# 6_Analog.net
KiCad netlist of a schematic drawn in Altium Designer
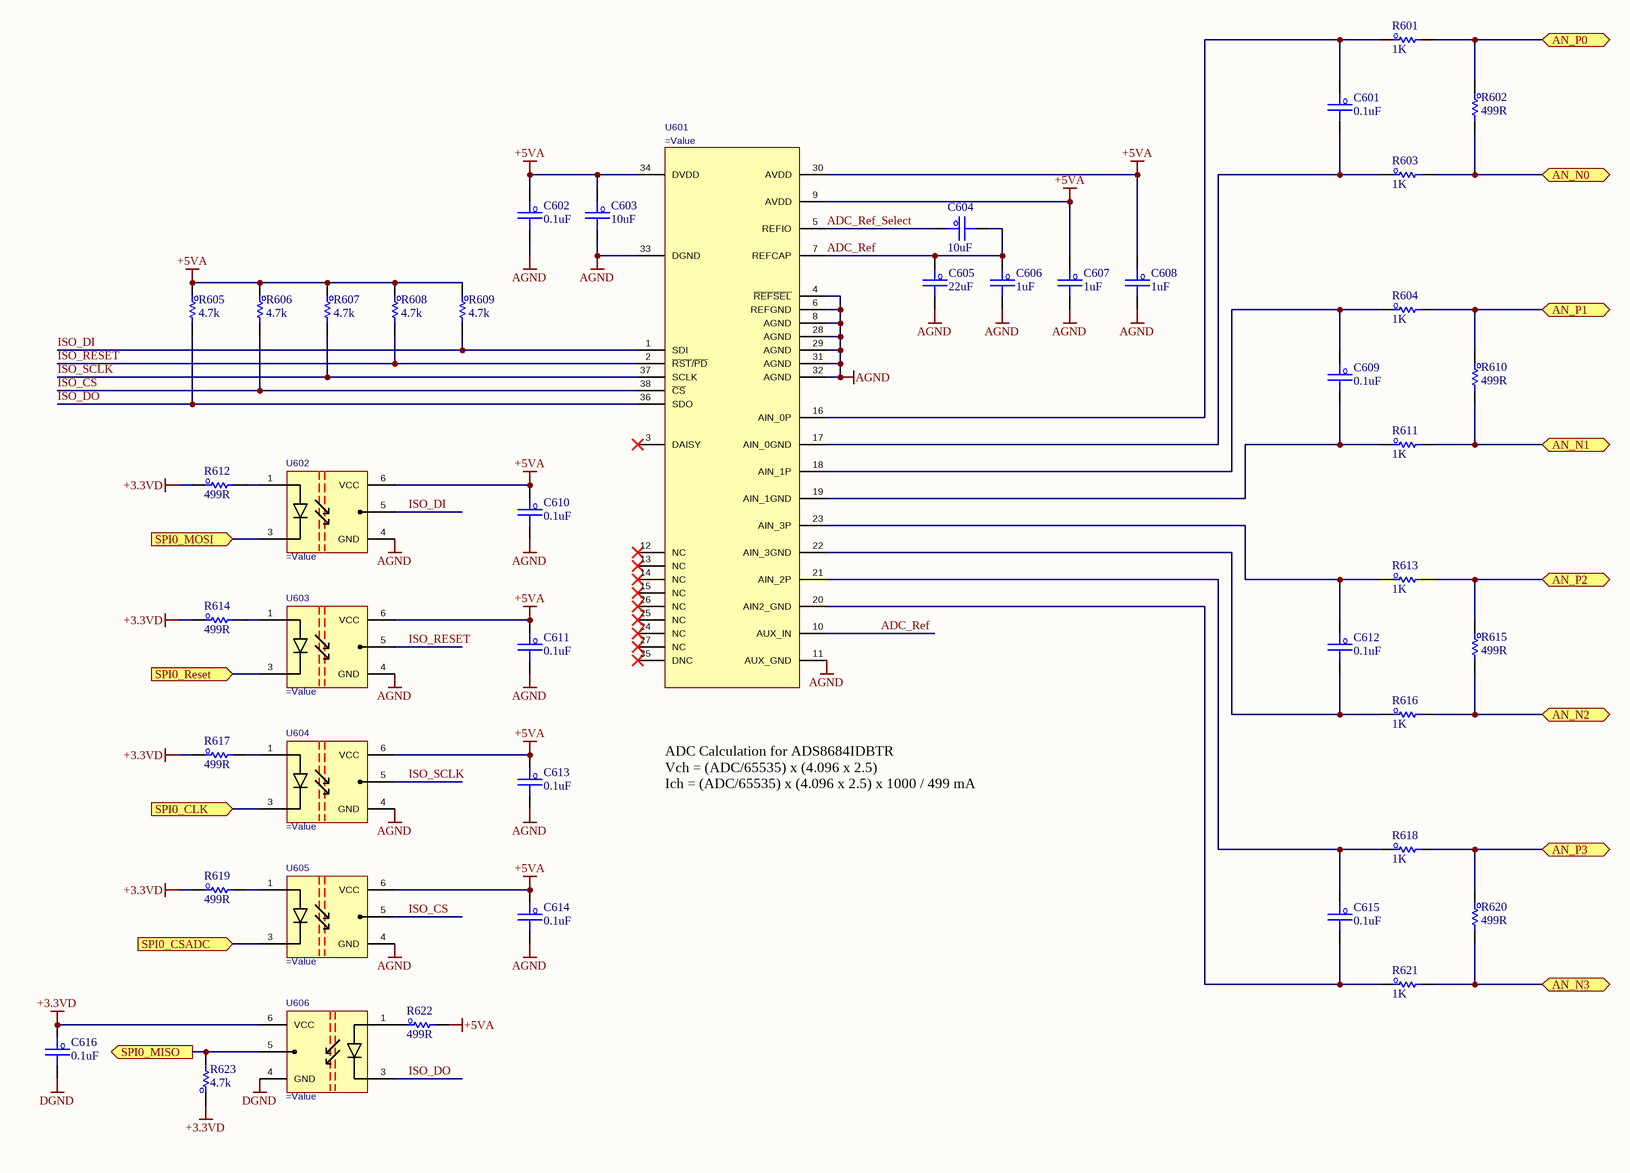
[diagram p0: 6_Analog.SchDoc]

(export (version "E")
  (design (tool "Eeschema 10.0.6"))
  (components
    (comp (ref "C601")
      (value "0.1uF")
      (footprint "C_0603")
      (description "CAP CER 0.1UF 50V X7R 0603")
      (fields (field (name "MANUFACTURER") "KEMET") (field (name "PARTNUMBER") "C0603C104K5RACTU"))
      (libsource (lib "UUSymbol") (part "C_Capacitor"))
    )
    (comp (ref "C602")
      (value "0.1uF")
      (footprint "C_0603")
      (description "CAP CER 0.1UF 50V X7R 0603")
      (fields (field (name "MANUFACTURER") "KEMET") (field (name "PARTNUMBER") "C0603C104K5RACTU"))
      (libsource (lib "UUSymbol") (part "C_Capacitor"))
    )
    (comp (ref "C603")
      (value "10uF")
      (footprint "C_0603")
      (description "CAP CER 10UF 10V X6S 0603")
      (fields
        (field (name "MANUFACTURER") "Murata Electronics")
        (field (name "PARTNUMBER") "GRT188C81A106ME13D")
      )
      (libsource (lib "UUSymbol") (part "C_Capacitor"))
    )
    (comp (ref "C604")
      (value "10uF")
      (footprint "C_0603")
      (description "CAP CER 10UF 10V X6S 0603")
      (fields
        (field (name "MANUFACTURER") "Murata Electronics")
        (field (name "PARTNUMBER") "GRT188C81A106ME13D")
      )
      (libsource (lib "UUSymbol") (part "C_Capacitor"))
    )
    (comp (ref "C605")
      (value "22uF")
      (footprint "C_0603")
      (description "CAP CER 22UF 10V X5R 0603")
      (fields
        (field (name "MANUFACTURER") "Murata Electronics")
        (field (name "PARTNUMBER") "GRM187R61A226ME15D")
      )
      (libsource (lib "UUSymbol") (part "C_Capacitor"))
    )
    (comp (ref "C606")
      (value "1uF")
      (footprint "C_0603")
      (description "CAP CER 1UF 50V X5R 0603")
      (fields
        (field (name "MANUFACTURER") "Murata Electronics")
        (field (name "PARTNUMBER") "GRT188R61H105KE13D")
      )
      (libsource (lib "UUSymbol") (part "C_Capacitor"))
    )
    (comp (ref "C607")
      (value "1uF")
      (footprint "C_0603")
      (description "CAP CER 1UF 50V X5R 0603")
      (fields
        (field (name "MANUFACTURER") "Murata Electronics")
        (field (name "PARTNUMBER") "GRT188R61H105KE13D")
      )
      (libsource (lib "UUSymbol") (part "C_Capacitor"))
    )
    (comp (ref "C608")
      (value "1uF")
      (footprint "C_0603")
      (description "CAP CER 1UF 50V X5R 0603")
      (fields
        (field (name "MANUFACTURER") "Murata Electronics")
        (field (name "PARTNUMBER") "GRT188R61H105KE13D")
      )
      (libsource (lib "UUSymbol") (part "C_Capacitor"))
    )
    (comp (ref "C609")
      (value "0.1uF")
      (footprint "C_0603")
      (description "CAP CER 0.1UF 50V X7R 0603")
      (fields (field (name "MANUFACTURER") "KEMET") (field (name "PARTNUMBER") "C0603C104K5RACTU"))
      (libsource (lib "UUSymbol") (part "C_Capacitor"))
    )
    (comp (ref "C610")
      (value "0.1uF")
      (footprint "C_0603")
      (description "CAP CER 0.1UF 50V X7R 0603")
      (fields (field (name "MANUFACTURER") "KEMET") (field (name "PARTNUMBER") "C0603C104K5RACTU"))
      (libsource (lib "UUSymbol") (part "C_Capacitor"))
    )
    (comp (ref "C611")
      (value "0.1uF")
      (footprint "C_0603")
      (description "CAP CER 0.1UF 50V X7R 0603")
      (fields (field (name "MANUFACTURER") "KEMET") (field (name "PARTNUMBER") "C0603C104K5RACTU"))
      (libsource (lib "UUSymbol") (part "C_Capacitor"))
    )
    (comp (ref "C612")
      (value "0.1uF")
      (footprint "C_0603")
      (description "CAP CER 0.1UF 50V X7R 0603")
      (fields (field (name "MANUFACTURER") "KEMET") (field (name "PARTNUMBER") "C0603C104K5RACTU"))
      (libsource (lib "UUSymbol") (part "C_Capacitor"))
    )
    (comp (ref "C613")
      (value "0.1uF")
      (footprint "C_0603")
      (description "CAP CER 0.1UF 50V X7R 0603")
      (fields (field (name "MANUFACTURER") "KEMET") (field (name "PARTNUMBER") "C0603C104K5RACTU"))
      (libsource (lib "UUSymbol") (part "C_Capacitor"))
    )
    (comp (ref "C614")
      (value "0.1uF")
      (footprint "C_0603")
      (description "CAP CER 0.1UF 50V X7R 0603")
      (fields (field (name "MANUFACTURER") "KEMET") (field (name "PARTNUMBER") "C0603C104K5RACTU"))
      (libsource (lib "UUSymbol") (part "C_Capacitor"))
    )
    (comp (ref "C615")
      (value "0.1uF")
      (footprint "C_0603")
      (description "CAP CER 0.1UF 50V X7R 0603")
      (fields (field (name "MANUFACTURER") "KEMET") (field (name "PARTNUMBER") "C0603C104K5RACTU"))
      (libsource (lib "UUSymbol") (part "C_Capacitor"))
    )
    (comp (ref "C616")
      (value "0.1uF")
      (footprint "C_0603")
      (description "CAP CER 0.1UF 50V X7R 0603")
      (fields (field (name "MANUFACTURER") "KEMET") (field (name "PARTNUMBER") "C0603C104K5RACTU"))
      (libsource (lib "UUSymbol") (part "C_Capacitor"))
    )
    (comp (ref "R601")
      (value "1K")
      (footprint "R_0603")
      (description "RES SMD 1K OHM 5% 1/10W 0603")
      (fields (field (name "MANUFACTURER") "Vishay Dale") (field (name "PARTNUMBER") "CRCW06031K00JNEA"))
      (libsource (lib "UUSymbol") (part "R_Resister"))
    )
    (comp (ref "R602")
      (value "499R")
      (footprint "R_0603")
      (description "RES SMD 499 OHM 1% 1/3W 0603")
      (fields (field (name "MANUFACTURER") "Vishay Dale") (field (name "PARTNUMBER") "CRCW0603499RFKEAHP"))
      (libsource (lib "UUSymbol") (part "R_Resister"))
    )
    (comp (ref "R603")
      (value "1K")
      (footprint "R_0603")
      (description "RES SMD 1K OHM 5% 1/10W 0603")
      (fields (field (name "MANUFACTURER") "Vishay Dale") (field (name "PARTNUMBER") "CRCW06031K00JNEA"))
      (libsource (lib "UUSymbol") (part "R_Resister"))
    )
    (comp (ref "R604")
      (value "1K")
      (footprint "R_0603")
      (description "RES SMD 1K OHM 5% 1/10W 0603")
      (fields (field (name "MANUFACTURER") "Vishay Dale") (field (name "PARTNUMBER") "CRCW06031K00JNEA"))
      (libsource (lib "UUSymbol") (part "R_Resister"))
    )
    (comp (ref "R605")
      (value "4.7k")
      (footprint "R_0603")
      (description "RES 4.7K OHM 5% 1/10W 0603")
      (fields (field (name "MANUFACTURER") "Vishay Dale") (field (name "PARTNUMBER") "CRCW06034K70JNEBC"))
      (libsource (lib "UUSymbol") (part "R_Resister"))
    )
    (comp (ref "R606")
      (value "4.7k")
      (footprint "R_0603")
      (description "RES 4.7K OHM 5% 1/10W 0603")
      (fields (field (name "MANUFACTURER") "Vishay Dale") (field (name "PARTNUMBER") "CRCW06034K70JNEBC"))
      (libsource (lib "UUSymbol") (part "R_Resister"))
    )
    (comp (ref "R607")
      (value "4.7k")
      (footprint "R_0603")
      (description "RES 4.7K OHM 5% 1/10W 0603")
      (fields (field (name "MANUFACTURER") "Vishay Dale") (field (name "PARTNUMBER") "CRCW06034K70JNEBC"))
      (libsource (lib "UUSymbol") (part "R_Resister"))
    )
    (comp (ref "R608")
      (value "4.7k")
      (footprint "R_0603")
      (description "RES 4.7K OHM 5% 1/10W 0603")
      (fields (field (name "MANUFACTURER") "Vishay Dale") (field (name "PARTNUMBER") "CRCW06034K70JNEBC"))
      (libsource (lib "UUSymbol") (part "R_Resister"))
    )
    (comp (ref "R609")
      (value "4.7k")
      (footprint "R_0603")
      (description "RES 4.7K OHM 5% 1/10W 0603")
      (fields (field (name "MANUFACTURER") "Vishay Dale") (field (name "PARTNUMBER") "CRCW06034K70JNEBC"))
      (libsource (lib "UUSymbol") (part "R_Resister"))
    )
    (comp (ref "R610")
      (value "499R")
      (footprint "R_0603")
      (description "RES SMD 499 OHM 1% 1/3W 0603")
      (fields (field (name "MANUFACTURER") "Vishay Dale") (field (name "PARTNUMBER") "CRCW0603499RFKEAHP"))
      (libsource (lib "UUSymbol") (part "R_Resister"))
    )
    (comp (ref "R611")
      (value "1K")
      (footprint "R_0603")
      (description "RES SMD 1K OHM 5% 1/10W 0603")
      (fields (field (name "MANUFACTURER") "Vishay Dale") (field (name "PARTNUMBER") "CRCW06031K00JNEA"))
      (libsource (lib "UUSymbol") (part "R_Resister"))
    )
    (comp (ref "R612")
      (value "499R")
      (footprint "R_0603")
      (description "RES 499 OHM 1% 1/10W 0603")
      (fields (field (name "MANUFACTURER") "Vishay Dale") (field (name "PARTNUMBER") "CRCW0603499RFKEAC"))
      (libsource (lib "UUSymbol") (part "R_Resister"))
    )
    (comp (ref "R613")
      (value "1K")
      (footprint "R_0603")
      (description "RES SMD 1K OHM 5% 1/10W 0603")
      (fields (field (name "MANUFACTURER") "Vishay Dale") (field (name "PARTNUMBER") "CRCW06031K00JNEA"))
      (libsource (lib "UUSymbol") (part "R_Resister"))
    )
    (comp (ref "R614")
      (value "499R")
      (footprint "R_0603")
      (description "RES 499 OHM 1% 1/10W 0603")
      (fields (field (name "MANUFACTURER") "Vishay Dale") (field (name "PARTNUMBER") "CRCW0603499RFKEAC"))
      (libsource (lib "UUSymbol") (part "R_Resister"))
    )
    (comp (ref "R615")
      (value "499R")
      (footprint "R_0603")
      (description "RES SMD 499 OHM 1% 1/3W 0603")
      (fields (field (name "MANUFACTURER") "Vishay Dale") (field (name "PARTNUMBER") "CRCW0603499RFKEAHP"))
      (libsource (lib "UUSymbol") (part "R_Resister"))
    )
    (comp (ref "R616")
      (value "1K")
      (footprint "R_0603")
      (description "RES SMD 1K OHM 5% 1/10W 0603")
      (fields (field (name "MANUFACTURER") "Vishay Dale") (field (name "PARTNUMBER") "CRCW06031K00JNEA"))
      (libsource (lib "UUSymbol") (part "R_Resister"))
    )
    (comp (ref "R617")
      (value "499R")
      (footprint "R_0603")
      (description "RES 499 OHM 1% 1/10W 0603")
      (fields (field (name "MANUFACTURER") "Vishay Dale") (field (name "PARTNUMBER") "CRCW0603499RFKEAC"))
      (libsource (lib "UUSymbol") (part "R_Resister"))
    )
    (comp (ref "R618")
      (value "1K")
      (footprint "R_0603")
      (description "RES SMD 1K OHM 5% 1/10W 0603")
      (fields (field (name "MANUFACTURER") "Vishay Dale") (field (name "PARTNUMBER") "CRCW06031K00JNEA"))
      (libsource (lib "UUSymbol") (part "R_Resister"))
    )
    (comp (ref "R619")
      (value "499R")
      (footprint "R_0603")
      (description "RES 499 OHM 1% 1/10W 0603")
      (fields (field (name "MANUFACTURER") "Vishay Dale") (field (name "PARTNUMBER") "CRCW0603499RFKEAC"))
      (libsource (lib "UUSymbol") (part "R_Resister"))
    )
    (comp (ref "R620")
      (value "499R")
      (footprint "R_0603")
      (description "RES SMD 499 OHM 1% 1/3W 0603")
      (fields (field (name "MANUFACTURER") "Vishay Dale") (field (name "PARTNUMBER") "CRCW0603499RFKEAHP"))
      (libsource (lib "UUSymbol") (part "R_Resister"))
    )
    (comp (ref "R621")
      (value "1K")
      (footprint "R_0603")
      (description "RES SMD 1K OHM 5% 1/10W 0603")
      (fields (field (name "MANUFACTURER") "Vishay Dale") (field (name "PARTNUMBER") "CRCW06031K00JNEA"))
      (libsource (lib "UUSymbol") (part "R_Resister"))
    )
    (comp (ref "R622")
      (value "499R")
      (footprint "R_0603")
      (description "RES 499 OHM 1% 1/10W 0603")
      (fields (field (name "MANUFACTURER") "Vishay Dale") (field (name "PARTNUMBER") "CRCW0603499RFKEAC"))
      (libsource (lib "UUSymbol") (part "R_Resister"))
    )
    (comp (ref "R623")
      (value "4.7k")
      (footprint "R_0603")
      (description "RES 4.7K OHM 5% 1/10W 0603")
      (fields (field (name "MANUFACTURER") "Vishay Dale") (field (name "PARTNUMBER") "CRCW06034K70JNEBC"))
      (libsource (lib "UUSymbol") (part "R_Resister"))
    )
    (comp (ref "U601")
      (value "~")
      (footprint "DBT0038A_N_TEX")
      (description "IC ADC 16BIT SAR 38TSSOP")
      (fields (field (name "MANUFACTURER") "Texas Instruments") (field (name "PARTNUMBER") "ADS8684IDBTR"))
      (libsource (lib "UUSymbol") (part "IC_ADC_ADS8684IDBTR"))
    )
    (comp (ref "U602")
      (value "~")
      (footprint "5PIN SO6_TOS")
      (description "OPTOISO 5KV PUSH PULL SO6L")
      (fields
        (field (name "MANUFACTURER") "Toshiba Semiconductor and Storage")
        (field (name "PARTNUMBER") "TLP2362(TPL,E(T")
      )
      (libsource (lib "") (part "IC_OPTO_TLP109(TPR,E)_1"))
    )
    (comp (ref "U603")
      (value "~")
      (footprint "5PIN SO6_TOS")
      (description "OPTOISO 5KV PUSH PULL SO6L")
      (fields
        (field (name "MANUFACTURER") "Toshiba Semiconductor and Storage")
        (field (name "PARTNUMBER") "TLP2362(TPL,E(T")
      )
      (libsource (lib "") (part "IC_OPTO_TLP109(TPR,E)_1"))
    )
    (comp (ref "U604")
      (value "~")
      (footprint "5PIN SO6_TOS")
      (description "OPTOISO 5KV PUSH PULL SO6L")
      (fields
        (field (name "MANUFACTURER") "Toshiba Semiconductor and Storage")
        (field (name "PARTNUMBER") "TLP2362(TPL,E(T")
      )
      (libsource (lib "") (part "IC_OPTO_TLP109(TPR,E)_1"))
    )
    (comp (ref "U605")
      (value "~")
      (footprint "5PIN SO6_TOS")
      (description "OPTOISO 5KV PUSH PULL SO6L")
      (fields
        (field (name "MANUFACTURER") "Toshiba Semiconductor and Storage")
        (field (name "PARTNUMBER") "TLP2362(TPL,E(T")
      )
      (libsource (lib "") (part "IC_OPTO_TLP109(TPR,E)_1"))
    )
    (comp (ref "U606")
      (value "~")
      (footprint "5PIN SO6_TOS")
      (description "OPTOISO 5KV PUSH PULL SO6L")
      (fields
        (field (name "MANUFACTURER") "Toshiba Semiconductor and Storage")
        (field (name "PARTNUMBER") "TLP2362(TPL,E(T")
      )
      (libsource (lib "UUSymbol") (part "IC_OPTO_TLP109(TPR,E)"))
    )
  )
  (nets
    (net (code "1") (name "+3.3VD") (class "Default")
      (node (ref "C616") (pin "1") (pinfunction "1_1") (pintype "passive"))
      (node (ref "R612") (pin "1") (pinfunction "1_1") (pintype "passive"))
      (node (ref "R614") (pin "1") (pinfunction "1_1") (pintype "passive"))
      (node (ref "R617") (pin "1") (pinfunction "1_1") (pintype "passive"))
      (node (ref "R619") (pin "1") (pinfunction "1_1") (pintype "passive"))
      (node (ref "R623") (pin "1") (pinfunction "1_1") (pintype "passive"))
      (node (ref "U606") (pin "6") (pinfunction "VCC_6") (pintype "passive"))
    )
    (net (code "2") (name "+5VA") (class "Default")
      (node (ref "C602") (pin "1") (pinfunction "1_1") (pintype "passive"))
      (node (ref "C603") (pin "1") (pinfunction "1_1") (pintype "passive"))
      (node (ref "C607") (pin "1") (pinfunction "1_1") (pintype "passive"))
      (node (ref "C608") (pin "1") (pinfunction "1_1") (pintype "passive"))
      (node (ref "C610") (pin "1") (pinfunction "1_1") (pintype "passive"))
      (node (ref "C611") (pin "1") (pinfunction "1_1") (pintype "passive"))
      (node (ref "C613") (pin "1") (pinfunction "1_1") (pintype "passive"))
      (node (ref "C614") (pin "1") (pinfunction "1_1") (pintype "passive"))
      (node (ref "R605") (pin "1") (pinfunction "1_1") (pintype "passive"))
      (node (ref "R606") (pin "1") (pinfunction "1_1") (pintype "passive"))
      (node (ref "R607") (pin "1") (pinfunction "1_1") (pintype "passive"))
      (node (ref "R608") (pin "1") (pinfunction "1_1") (pintype "passive"))
      (node (ref "R609") (pin "1") (pinfunction "1_1") (pintype "passive"))
      (node (ref "R622") (pin "2") (pinfunction "2_2") (pintype "passive"))
      (node (ref "U601") (pin "30") (pinfunction "AVDD_30") (pintype "passive"))
      (node (ref "U601") (pin "34") (pinfunction "DVDD_34") (pintype "passive"))
      (node (ref "U601") (pin "9") (pinfunction "AVDD_9") (pintype "passive"))
      (node (ref "U602") (pin "6") (pinfunction "VCC_6") (pintype "passive"))
      (node (ref "U603") (pin "6") (pinfunction "VCC_6") (pintype "passive"))
      (node (ref "U604") (pin "6") (pinfunction "VCC_6") (pintype "passive"))
      (node (ref "U605") (pin "6") (pinfunction "VCC_6") (pintype "passive"))
    )
    (net (code "3") (name "/ADC_Ref") (class "Default")
      (node (ref "C604") (pin "2") (pinfunction "2_2") (pintype "passive"))
      (node (ref "C605") (pin "1") (pinfunction "1_1") (pintype "passive"))
      (node (ref "C606") (pin "1") (pinfunction "1_1") (pintype "passive"))
      (node (ref "U601") (pin "10") (pinfunction "AUX_IN_10") (pintype "passive"))
      (node (ref "U601") (pin "7") (pinfunction "REFCAP_7") (pintype "passive"))
    )
    (net (code "4") (name "/ADC_Ref_Select") (class "Default")
      (node (ref "C604") (pin "1") (pinfunction "1_1") (pintype "passive"))
      (node (ref "U601") (pin "5") (pinfunction "REFIO_5") (pintype "passive"))
    )
    (net (code "5") (name "/AN_N0") (class "Default")
      (node (ref "R602") (pin "2") (pinfunction "2_2") (pintype "passive"))
      (node (ref "R603") (pin "2") (pinfunction "2_2") (pintype "passive"))
    )
    (net (code "6") (name "/AN_N1") (class "Default")
      (node (ref "R610") (pin "2") (pinfunction "2_2") (pintype "passive"))
      (node (ref "R611") (pin "2") (pinfunction "2_2") (pintype "passive"))
    )
    (net (code "7") (name "/AN_N2") (class "Default")
      (node (ref "R615") (pin "2") (pinfunction "2_2") (pintype "passive"))
      (node (ref "R616") (pin "2") (pinfunction "2_2") (pintype "passive"))
    )
    (net (code "8") (name "/AN_N3") (class "Default")
      (node (ref "R620") (pin "2") (pinfunction "2_2") (pintype "passive"))
      (node (ref "R621") (pin "2") (pinfunction "2_2") (pintype "passive"))
    )
    (net (code "9") (name "/AN_P0") (class "Default")
      (node (ref "R601") (pin "2") (pinfunction "2_2") (pintype "passive"))
      (node (ref "R602") (pin "1") (pinfunction "1_1") (pintype "passive"))
    )
    (net (code "10") (name "/AN_P1") (class "Default")
      (node (ref "R604") (pin "2") (pinfunction "2_2") (pintype "passive"))
      (node (ref "R610") (pin "1") (pinfunction "1_1") (pintype "passive"))
    )
    (net (code "11") (name "/AN_P2") (class "Default")
      (node (ref "R613") (pin "2") (pinfunction "2_2") (pintype "passive"))
      (node (ref "R615") (pin "1") (pinfunction "1_1") (pintype "passive"))
    )
    (net (code "12") (name "/AN_P3") (class "Default")
      (node (ref "R618") (pin "2") (pinfunction "2_2") (pintype "passive"))
      (node (ref "R620") (pin "1") (pinfunction "1_1") (pintype "passive"))
    )
    (net (code "13") (name "/ISO_CS") (class "Default")
      (node (ref "R606") (pin "2") (pinfunction "2_2") (pintype "passive"))
      (node (ref "U601") (pin "38") (pinfunction "~{CS}_38") (pintype "passive"))
      (node (ref "U605") (pin "5") (pinfunction "O1_5") (pintype "passive"))
    )
    (net (code "14") (name "/ISO_DI") (class "Default")
      (node (ref "R609") (pin "2") (pinfunction "2_2") (pintype "passive"))
      (node (ref "U601") (pin "1") (pinfunction "SDI_1") (pintype "passive"))
      (node (ref "U602") (pin "5") (pinfunction "O1_5") (pintype "passive"))
    )
    (net (code "15") (name "/ISO_DO") (class "Default")
      (node (ref "R605") (pin "2") (pinfunction "2_2") (pintype "passive"))
      (node (ref "U601") (pin "36") (pinfunction "SDO_36") (pintype "passive"))
      (node (ref "U606") (pin "3") (pinfunction "A_3") (pintype "passive"))
    )
    (net (code "16") (name "/ISO_RESET") (class "Default")
      (node (ref "R608") (pin "2") (pinfunction "2_2") (pintype "passive"))
      (node (ref "U601") (pin "2") (pinfunction "~{RST}/~{PD}_2") (pintype "passive"))
      (node (ref "U603") (pin "5") (pinfunction "O1_5") (pintype "passive"))
    )
    (net (code "17") (name "/ISO_SCLK") (class "Default")
      (node (ref "R607") (pin "2") (pinfunction "2_2") (pintype "passive"))
      (node (ref "U601") (pin "37") (pinfunction "SCLK_37") (pintype "passive"))
      (node (ref "U604") (pin "5") (pinfunction "O1_5") (pintype "passive"))
    )
    (net (code "18") (name "/SPI0_CLK") (class "Default")
      (node (ref "U604") (pin "3") (pinfunction "A_3") (pintype "passive"))
    )
    (net (code "19") (name "/SPI0_CSADC") (class "Default")
      (node (ref "U605") (pin "3") (pinfunction "A_3") (pintype "passive"))
    )
    (net (code "20") (name "/SPI0_MISO") (class "Default")
      (node (ref "R623") (pin "2") (pinfunction "2_2") (pintype "passive"))
      (node (ref "U606") (pin "5") (pinfunction "O1_5") (pintype "passive"))
    )
    (net (code "21") (name "/SPI0_MOSI") (class "Default")
      (node (ref "U602") (pin "3") (pinfunction "A_3") (pintype "passive"))
    )
    (net (code "22") (name "/SPI0_Reset") (class "Default")
      (node (ref "U603") (pin "3") (pinfunction "A_3") (pintype "passive"))
    )
    (net (code "23") (name "AGND") (class "Default")
      (node (ref "C602") (pin "2") (pinfunction "2_2") (pintype "passive"))
      (node (ref "C603") (pin "2") (pinfunction "2_2") (pintype "passive"))
      (node (ref "C605") (pin "2") (pinfunction "2_2") (pintype "passive"))
      (node (ref "C606") (pin "2") (pinfunction "2_2") (pintype "passive"))
      (node (ref "C607") (pin "2") (pinfunction "2_2") (pintype "passive"))
      (node (ref "C608") (pin "2") (pinfunction "2_2") (pintype "passive"))
      (node (ref "C610") (pin "2") (pinfunction "2_2") (pintype "passive"))
      (node (ref "C611") (pin "2") (pinfunction "2_2") (pintype "passive"))
      (node (ref "C613") (pin "2") (pinfunction "2_2") (pintype "passive"))
      (node (ref "C614") (pin "2") (pinfunction "2_2") (pintype "passive"))
      (node (ref "U601") (pin "11") (pinfunction "AUX_GND_11") (pintype "passive"))
      (node (ref "U601") (pin "28") (pinfunction "AGND_28") (pintype "passive"))
      (node (ref "U601") (pin "29") (pinfunction "AGND_29") (pintype "passive"))
      (node (ref "U601") (pin "31") (pinfunction "AGND_31") (pintype "passive"))
      (node (ref "U601") (pin "32") (pinfunction "AGND_32") (pintype "passive"))
      (node (ref "U601") (pin "33") (pinfunction "DGND_33") (pintype "passive"))
      (node (ref "U601") (pin "4") (pinfunction "~{REFSEL}_4") (pintype "passive"))
      (node (ref "U601") (pin "6") (pinfunction "REFGND_6") (pintype "passive"))
      (node (ref "U601") (pin "8") (pinfunction "AGND_8") (pintype "passive"))
      (node (ref "U602") (pin "4") (pinfunction "GND_4") (pintype "passive"))
      (node (ref "U603") (pin "4") (pinfunction "GND_4") (pintype "passive"))
      (node (ref "U604") (pin "4") (pinfunction "GND_4") (pintype "passive"))
      (node (ref "U605") (pin "4") (pinfunction "GND_4") (pintype "passive"))
    )
    (net (code "24") (name "DGND") (class "Default")
      (node (ref "C616") (pin "2") (pinfunction "2_2") (pintype "passive"))
      (node (ref "U606") (pin "4") (pinfunction "GND_4") (pintype "passive"))
    )
    (net (code "25") (name "Net-(R612-Pad2)") (class "Default")
      (node (ref "R612") (pin "2") (pinfunction "2_2") (pintype "passive"))
      (node (ref "U602") (pin "1") (pinfunction "A_1") (pintype "passive"))
    )
    (net (code "26") (name "Net-(R614-Pad2)") (class "Default")
      (node (ref "R614") (pin "2") (pinfunction "2_2") (pintype "passive"))
      (node (ref "U603") (pin "1") (pinfunction "A_1") (pintype "passive"))
    )
    (net (code "27") (name "Net-(R617-Pad2)") (class "Default")
      (node (ref "R617") (pin "2") (pinfunction "2_2") (pintype "passive"))
      (node (ref "U604") (pin "1") (pinfunction "A_1") (pintype "passive"))
    )
    (net (code "28") (name "Net-(R619-Pad2)") (class "Default")
      (node (ref "R619") (pin "2") (pinfunction "2_2") (pintype "passive"))
      (node (ref "U605") (pin "1") (pinfunction "A_1") (pintype "passive"))
    )
    (net (code "29") (name "Net-(R622-Pad1)") (class "Default")
      (node (ref "R622") (pin "1") (pinfunction "1_1") (pintype "passive"))
      (node (ref "U606") (pin "1") (pinfunction "A_1") (pintype "passive"))
    )
    (net (code "30") (name "Net-(U601-AIN2_GND)") (class "Default")
      (node (ref "C615") (pin "2") (pinfunction "2_2") (pintype "passive"))
      (node (ref "R621") (pin "1") (pinfunction "1_1") (pintype "passive"))
      (node (ref "U601") (pin "20") (pinfunction "AIN2_GND_20") (pintype "passive"))
    )
    (net (code "31") (name "Net-(U601-AIN_0GND)") (class "Default")
      (node (ref "C601") (pin "2") (pinfunction "2_2") (pintype "passive"))
      (node (ref "R603") (pin "1") (pinfunction "1_1") (pintype "passive"))
      (node (ref "U601") (pin "17") (pinfunction "AIN_0GND_17") (pintype "passive"))
    )
    (net (code "32") (name "Net-(U601-AIN_0P)") (class "Default")
      (node (ref "C601") (pin "1") (pinfunction "1_1") (pintype "passive"))
      (node (ref "R601") (pin "1") (pinfunction "1_1") (pintype "passive"))
      (node (ref "U601") (pin "16") (pinfunction "AIN_0P_16") (pintype "passive"))
    )
    (net (code "33") (name "Net-(U601-AIN_1GND)") (class "Default")
      (node (ref "C609") (pin "2") (pinfunction "2_2") (pintype "passive"))
      (node (ref "R611") (pin "1") (pinfunction "1_1") (pintype "passive"))
      (node (ref "U601") (pin "19") (pinfunction "AIN_1GND_19") (pintype "passive"))
    )
    (net (code "34") (name "Net-(U601-AIN_1P)") (class "Default")
      (node (ref "C609") (pin "1") (pinfunction "1_1") (pintype "passive"))
      (node (ref "R604") (pin "1") (pinfunction "1_1") (pintype "passive"))
      (node (ref "U601") (pin "18") (pinfunction "AIN_1P_18") (pintype "passive"))
    )
    (net (code "35") (name "Net-(U601-AIN_2P)") (class "Default")
      (node (ref "C615") (pin "1") (pinfunction "1_1") (pintype "passive"))
      (node (ref "R618") (pin "1") (pinfunction "1_1") (pintype "passive"))
      (node (ref "U601") (pin "21") (pinfunction "AIN_2P_21") (pintype "passive"))
    )
    (net (code "36") (name "Net-(U601-AIN_3GND)") (class "Default")
      (node (ref "C612") (pin "2") (pinfunction "2_2") (pintype "passive"))
      (node (ref "R616") (pin "1") (pinfunction "1_1") (pintype "passive"))
      (node (ref "U601") (pin "22") (pinfunction "AIN_3GND_22") (pintype "passive"))
    )
    (net (code "37") (name "Net-(U601-AIN_3P)") (class "Default")
      (node (ref "C612") (pin "1") (pinfunction "1_1") (pintype "passive"))
      (node (ref "R613") (pin "1") (pinfunction "1_1") (pintype "passive"))
      (node (ref "U601") (pin "23") (pinfunction "AIN_3P_23") (pintype "passive"))
    )
    (net (code "38") (name "unconnected-(U601-DAISY-Pad3)") (class "Default")
      (node (ref "U601") (pin "3") (pinfunction "DAISY_3") (pintype "passive+no_connect"))
    )
    (net (code "39") (name "unconnected-(U601-DNC-Pad35)") (class "Default")
      (node (ref "U601") (pin "35") (pinfunction "DNC_35") (pintype "passive+no_connect"))
    )
    (net (code "40") (name "unconnected-(U601-NC-Pad12)") (class "Default")
      (node (ref "U601") (pin "12") (pinfunction "NC_12") (pintype "passive+no_connect"))
    )
    (net (code "41") (name "unconnected-(U601-NC-Pad13)") (class "Default")
      (node (ref "U601") (pin "13") (pinfunction "NC_13") (pintype "passive+no_connect"))
    )
    (net (code "42") (name "unconnected-(U601-NC-Pad14)") (class "Default")
      (node (ref "U601") (pin "14") (pinfunction "NC_14") (pintype "passive+no_connect"))
    )
    (net (code "43") (name "unconnected-(U601-NC-Pad15)") (class "Default")
      (node (ref "U601") (pin "15") (pinfunction "NC_15") (pintype "passive+no_connect"))
    )
    (net (code "44") (name "unconnected-(U601-NC-Pad24)") (class "Default")
      (node (ref "U601") (pin "24") (pinfunction "NC_24") (pintype "passive+no_connect"))
    )
    (net (code "45") (name "unconnected-(U601-NC-Pad25)") (class "Default")
      (node (ref "U601") (pin "25") (pinfunction "NC_25") (pintype "passive+no_connect"))
    )
    (net (code "46") (name "unconnected-(U601-NC-Pad26)") (class "Default")
      (node (ref "U601") (pin "26") (pinfunction "NC_26") (pintype "passive+no_connect"))
    )
    (net (code "47") (name "unconnected-(U601-NC-Pad27)") (class "Default")
      (node (ref "U601") (pin "27") (pinfunction "NC_27") (pintype "passive+no_connect"))
    )
  )
)
